# sd_card_module.net
KiCad netlist of a schematic drawn in Altium Designer
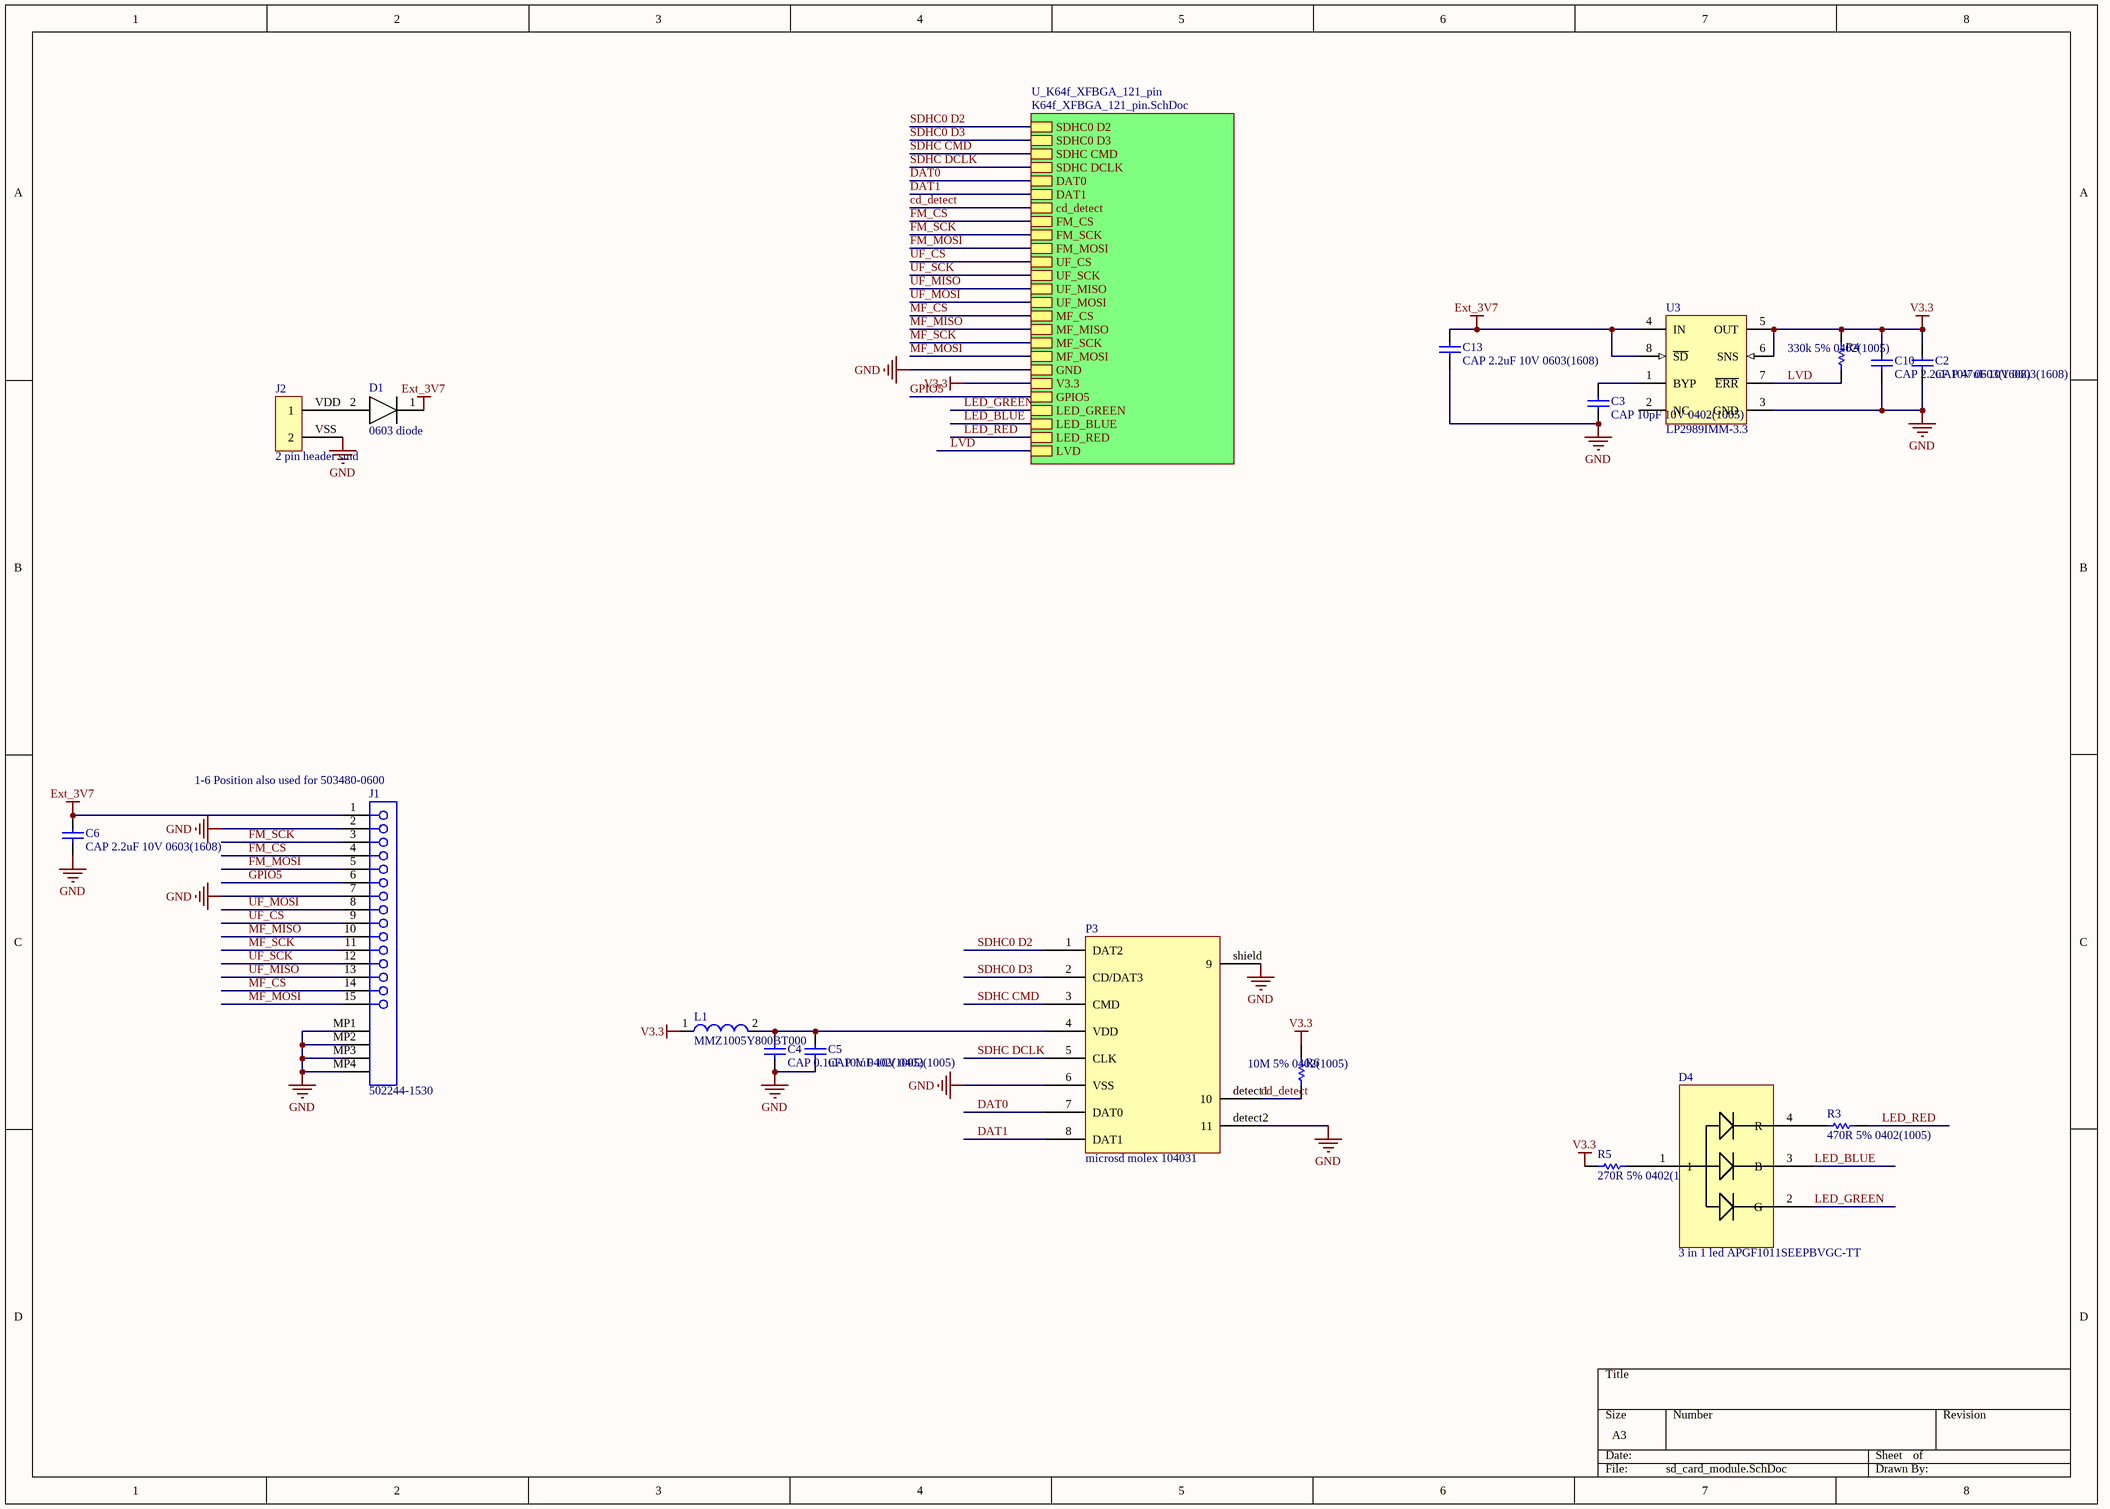
[diagram p0: sd_card_module.SchDoc]

(export (version "E")
  (design (tool "Eeschema 10.0.6"))
  (components
    (comp (ref "C2")
      (value "CAP 47uF 10V 0603(1608)")
      (footprint "CAPC0603(1608)100_M")
      (description "CAP 47uF 10V ±0.1pF 0603 (1608 Metric) Thickness 1mm SMD")
      (fields (field (name "TOLERANCE") "Â±0.1pF"))
      (libsource (lib "Altium Content Vault") (part "CMP-1035-00147-1"))
    )
    (comp (ref "C3")
      (value "CAP 10pF 10V 0402(1005)")
      (footprint "CAPC0402(1005)60_M")
      (description "CAP 10pF 10V ±0.1pF 0402 (1005 Metric) Thickness 0.6mm SMD")
      (fields (field (name "TOLERANCE") "Â±0.1pF"))
      (libsource (lib "Altium Content Vault") (part "CMP-1034-00013-1"))
    )
    (comp (ref "C4")
      (value "CAP 0.1uF 10V 0402(1005)")
      (footprint "CAPC0402(1005)60_M")
      (description "CAP 0.5pF 10V ±0.1uF 0402 (1005 Metric) Thickness 0.6mm SMD")
      (fields (field (name "TOLERANCE") "Â±0.1pF"))
      (libsource (lib "Altium Content Vault") (part "CMP-1034-00013-1"))
    )
    (comp (ref "C5")
      (value "CAP 1uF 10V 0402(1005)")
      (footprint "CAPC0402(1005)60_M")
      (description "CAP 1uF 10V ±1uF 0402 (1005 Metric) Thickness 0.6mm SMD")
      (fields (field (name "TOLERANCE") "Â±0.1pF"))
      (libsource (lib "Altium Content Vault") (part "CMP-1034-00013-1"))
    )
    (comp (ref "C6")
      (value "CAP 2.2uF 10V 0603(1608)")
      (footprint "CAPC0603(1608)100_M")
      (description "CAP 2.2uF 10V ±0.1pF 0603 (1608 Metric) Thickness 1mm SMD")
      (fields (field (name "TOLERANCE") "Â±0.1pF"))
      (libsource (lib "Altium Content Vault") (part "CMP-1035-00147-1"))
    )
    (comp (ref "C10")
      (value "CAP 2.2uF 10V 0603(1608)")
      (footprint "CAPC0603(1608)100_M")
      (description "CAP 2.2uF 10V ±0.1pF 0603 (1608 Metric) Thickness 1mm SMD")
      (fields (field (name "TOLERANCE") "Â±0.1pF"))
      (libsource (lib "Altium Content Vault") (part "CMP-1035-00147-1"))
    )
    (comp (ref "C13")
      (value "CAP 2.2uF 10V 0603(1608)")
      (footprint "CAPC0603(1608)100_M")
      (description "CAP 2.2uF 10V ±0.1pF 0603 (1608 Metric) Thickness 1mm SMD")
      (fields (field (name "TOLERANCE") "Â±0.1pF"))
      (libsource (lib "Altium Content Vault") (part "CMP-1035-00147-1"))
    )
    (comp (ref "D1")
      (value "0603 diode")
      (footprint "DIOC0603X03N")
      (libsource (lib "Senseback_lib") (part "0603 diode"))
    )
    (comp (ref "D4")
      (value "3 in 1 led APGF1011SEEPBVGC-TT")
      (footprint "APGF1011SEEPBVGC-TT")
      (libsource (lib "Senseback_lib") (part "3 in 1 led APGF1011SEEPBVGC-TT"))
    )
    (comp (ref "J1")
      (value "502244-1530")
      (footprint "MOLX-502244-1530 long_pins")
      (libsource (lib "USBridge") (part "MOLX-502244-1530"))
    )
    (comp (ref "J2")
      (value "2 pin header smd")
      (footprint "2 pin header picolock")
      (libsource (lib "Senseback_lib") (part "2 pin header smd"))
    )
    (comp (ref "L1")
      (value "MMZ1005Y800BT000")
      (footprint "SMD-0402")
      (description "EMI Filter Beads, Chips & Arrays 0402 80ohms 250mA HiSpd Signal Line")
      (libsource (lib "Altium Content Vault") (part "CMP-0220-00098-1"))
    )
    (comp (ref "P3")
      (value "microsd molex 104031")
      (footprint "MICROSD 104031 molex")
      (libsource (lib "Senseback_lib") (part "microsd molex 104031"))
    )
    (comp (ref "R3")
      (value "470R 5% 0402(1005)")
      (footprint "RESC0402(1005)_L")
      (description "470R 5% 0402 (1005 Metric)  SMD")
      (fields (field (name "TOLERANCE") "5 %") (field (name "POWER") "0.063 W"))
      (libsource (lib "Altium Content Vault") (part "CMP-1011-00090-1"))
    )
    (comp (ref "R4")
      (value "330k 5% 0402(1005)")
      (footprint "RESC0402(1005)_L")
      (description "330k 0.063W 5% 0402 (1005 Metric)  SMD")
      (fields (field (name "TOLERANCE") "5 %") (field (name "POWER") "0.063 W"))
      (libsource (lib "Altium Content Vault") (part "CMP-1011-00090-1"))
    )
    (comp (ref "R5")
      (value "270R 5% 0402(1005)")
      (footprint "RESC0402(1005)_L")
      (description "270R W 5% 0402 (1005 Metric)  SMD")
      (fields (field (name "TOLERANCE") "5 %") (field (name "POWER") "0.063 W"))
      (libsource (lib "Altium Content Vault") (part "CMP-1011-00090-1"))
    )
    (comp (ref "R6")
      (value "10M 5% 0402(1005)")
      (footprint "RESC0402(1005)_L")
      (description "10M 0.063W 5% 0402 (1005 Metric)  SMD")
      (fields (field (name "TOLERANCE") "5 %") (field (name "POWER") "0.063 W"))
      (libsource (lib "Altium Content Vault") (part "CMP-1011-00090-1"))
    )
    (comp (ref "U3")
      (value "LP2989IMM-3.3")
      (footprint "MUA08A_L")
      (description "Micropower/Low Noise, 500 mA Ultra Low-Dropout Regulator, 8-pin Mini SOIC")
      (fields (field (name "MANUFACTURER") "National Semiconductor"))
      (libsource (lib "Altium Content Vault") (part "PM-REG-LP2989-IL8"))
    )
  )
  (nets
    (net (code "1") (name "/DAT0") (class "Default")
      (node (ref "P3") (pin "7") (pinfunction "DAT0_7") (pintype "passive"))
    )
    (net (code "2") (name "/DAT1") (class "Default")
      (node (ref "P3") (pin "8") (pinfunction "DAT1_8") (pintype "passive"))
    )
    (net (code "3") (name "/FM_CS") (class "Default")
      (node (ref "J1") (pin "4") (pinfunction "4_4") (pintype "passive"))
    )
    (net (code "4") (name "/FM_MOSI") (class "Default")
      (node (ref "J1") (pin "5") (pinfunction "5_5") (pintype "passive"))
    )
    (net (code "5") (name "/FM_SCK") (class "Default")
      (node (ref "J1") (pin "3") (pinfunction "3_3") (pintype "passive"))
    )
    (net (code "6") (name "/GPIO5") (class "Default")
      (node (ref "J1") (pin "6") (pinfunction "6_6") (pintype "passive"))
    )
    (net (code "7") (name "/LED_BLUE") (class "Default")
      (node (ref "D4") (pin "3") (pinfunction "B_3") (pintype "passive"))
    )
    (net (code "8") (name "/LED_GREEN") (class "Default")
      (node (ref "D4") (pin "2") (pinfunction "G_2") (pintype "passive"))
    )
    (net (code "9") (name "/LED_RED") (class "Default")
      (node (ref "R3") (pin "2") (pinfunction "2_2") (pintype "passive"))
    )
    (net (code "10") (name "/LVD") (class "Default")
      (node (ref "R4") (pin "2") (pinfunction "2_2") (pintype "passive"))
      (node (ref "U3") (pin "7") (pinfunction "~{ERR}_7") (pintype "open_collector"))
    )
    (net (code "11") (name "/MF_CS") (class "Default")
      (node (ref "J1") (pin "14") (pinfunction "14_14") (pintype "passive"))
    )
    (net (code "12") (name "/MF_MISO") (class "Default")
      (node (ref "J1") (pin "10") (pinfunction "10_10") (pintype "passive"))
    )
    (net (code "13") (name "/MF_MOSI") (class "Default")
      (node (ref "J1") (pin "15") (pinfunction "15_15") (pintype "passive"))
    )
    (net (code "14") (name "/MF_SCK") (class "Default")
      (node (ref "J1") (pin "11") (pinfunction "11_11") (pintype "passive"))
    )
    (net (code "15") (name "/SDHC CMD") (class "Default")
      (node (ref "P3") (pin "3") (pinfunction "CMD_3") (pintype "passive"))
    )
    (net (code "16") (name "/SDHC DCLK") (class "Default")
      (node (ref "P3") (pin "5") (pinfunction "CLK_5") (pintype "passive"))
    )
    (net (code "17") (name "/SDHC0 D2") (class "Default")
      (node (ref "P3") (pin "1") (pinfunction "DAT2_1") (pintype "passive"))
    )
    (net (code "18") (name "/SDHC0 D3") (class "Default")
      (node (ref "P3") (pin "2") (pinfunction "CD/DAT3_2") (pintype "passive"))
    )
    (net (code "19") (name "/UF_CS") (class "Default")
      (node (ref "J1") (pin "9") (pinfunction "9_9") (pintype "passive"))
    )
    (net (code "20") (name "/UF_MISO") (class "Default")
      (node (ref "J1") (pin "13") (pinfunction "13_13") (pintype "passive"))
    )
    (net (code "21") (name "/UF_MOSI") (class "Default")
      (node (ref "J1") (pin "8") (pinfunction "8_8") (pintype "passive"))
    )
    (net (code "22") (name "/UF_SCK") (class "Default")
      (node (ref "J1") (pin "12") (pinfunction "12_12") (pintype "passive"))
    )
    (net (code "23") (name "/cd_detect") (class "Default")
      (node (ref "P3") (pin "detect1") (pinfunction "10_detect1") (pintype "passive"))
      (node (ref "R6") (pin "2") (pinfunction "2_2") (pintype "passive"))
    )
    (net (code "24") (name "Ext_3V7") (class "Default")
      (node (ref "C13") (pin "2") (pinfunction "2_2") (pintype "passive"))
      (node (ref "C6") (pin "2") (pinfunction "2_2") (pintype "passive"))
      (node (ref "D1") (pin "1") (pintype "passive"))
      (node (ref "J1") (pin "1") (pinfunction "1_1") (pintype "passive"))
      (node (ref "U3") (pin "4") (pinfunction "IN_4") (pintype "power_in"))
      (node (ref "U3") (pin "8") (pinfunction "~{SD}_8") (pintype "input"))
    )
    (net (code "25") (name "GND") (class "Default")
      (node (ref "C10") (pin "1") (pinfunction "1_1") (pintype "passive"))
      (node (ref "C13") (pin "1") (pinfunction "1_1") (pintype "passive"))
      (node (ref "C2") (pin "1") (pinfunction "1_1") (pintype "passive"))
      (node (ref "C3") (pin "1") (pinfunction "1_1") (pintype "passive"))
      (node (ref "C4") (pin "1") (pinfunction "1_1") (pintype "passive"))
      (node (ref "C5") (pin "1") (pinfunction "1_1") (pintype "passive"))
      (node (ref "C6") (pin "1") (pinfunction "1_1") (pintype "passive"))
      (node (ref "J1") (pin "2") (pinfunction "2_2") (pintype "passive"))
      (node (ref "J1") (pin "7") (pinfunction "7_7") (pintype "passive"))
      (node (ref "J1") (pin "MP1") (pinfunction "MP1_MP1") (pintype "passive"))
      (node (ref "J1") (pin "MP2") (pinfunction "MP2_MP2") (pintype "passive"))
      (node (ref "J1") (pin "MP3") (pinfunction "MP3_MP3") (pintype "passive"))
      (node (ref "J1") (pin "MP4") (pinfunction "MP4_MP4") (pintype "passive"))
      (node (ref "J2") (pin "VSS") (pinfunction "2_VSS") (pintype "passive"))
      (node (ref "P3") (pin "6") (pinfunction "VSS_6") (pintype "passive"))
      (node (ref "P3") (pin "detect2") (pinfunction "11_detect2") (pintype "passive"))
      (node (ref "P3") (pin "shield") (pinfunction "9_shield") (pintype "passive"))
      (node (ref "U3") (pin "3") (pinfunction "GND_3") (pintype "power_in"))
    )
    (net (code "26") (name "Net-(D4-Pad1)") (class "Default")
      (node (ref "D4") (pin "1") (pinfunction "1_1") (pintype "passive"))
      (node (ref "R5") (pin "2") (pinfunction "2_2") (pintype "passive"))
    )
    (net (code "27") (name "Net-(D4-R)") (class "Default")
      (node (ref "D4") (pin "4") (pinfunction "R_4") (pintype "passive"))
      (node (ref "R3") (pin "1") (pinfunction "1_1") (pintype "passive"))
    )
    (net (code "28") (name "Net-(J2-1)") (class "Default")
      (node (ref "D1") (pin "2") (pintype "passive"))
      (node (ref "J2") (pin "VDD") (pinfunction "1_VDD") (pintype "passive"))
    )
    (net (code "29") (name "Net-(P3-VDD)") (class "Default")
      (node (ref "C4") (pin "2") (pinfunction "2_2") (pintype "passive"))
      (node (ref "C5") (pin "2") (pinfunction "2_2") (pintype "passive"))
      (node (ref "L1") (pin "2") (pinfunction "2_2") (pintype "passive"))
      (node (ref "P3") (pin "4") (pinfunction "VDD_4") (pintype "passive"))
    )
    (net (code "30") (name "Net-(U3-BYP)") (class "Default")
      (node (ref "C3") (pin "2") (pinfunction "2_2") (pintype "passive"))
      (node (ref "U3") (pin "1") (pinfunction "BYP_1") (pintype "passive"))
    )
    (net (code "31") (name "V3.3") (class "Default")
      (node (ref "C10") (pin "2") (pinfunction "2_2") (pintype "passive"))
      (node (ref "C2") (pin "2") (pinfunction "2_2") (pintype "passive"))
      (node (ref "L1") (pin "1") (pinfunction "1_1") (pintype "passive"))
      (node (ref "R4") (pin "1") (pinfunction "1_1") (pintype "passive"))
      (node (ref "R5") (pin "1") (pinfunction "1_1") (pintype "passive"))
      (node (ref "R6") (pin "1") (pinfunction "1_1") (pintype "passive"))
      (node (ref "U3") (pin "5") (pinfunction "OUT_5") (pintype "power_in"))
      (node (ref "U3") (pin "6") (pinfunction "SNS_6") (pintype "input"))
    )
    (net (code "32") (name "unconnected-(U3-NC-Pad2)") (class "Default")
      (node (ref "U3") (pin "2") (pinfunction "NC_2") (pintype "passive"))
    )
  )
)
